# io-bus2.net
KiCad netlist of a schematic drawn in Altium Designer
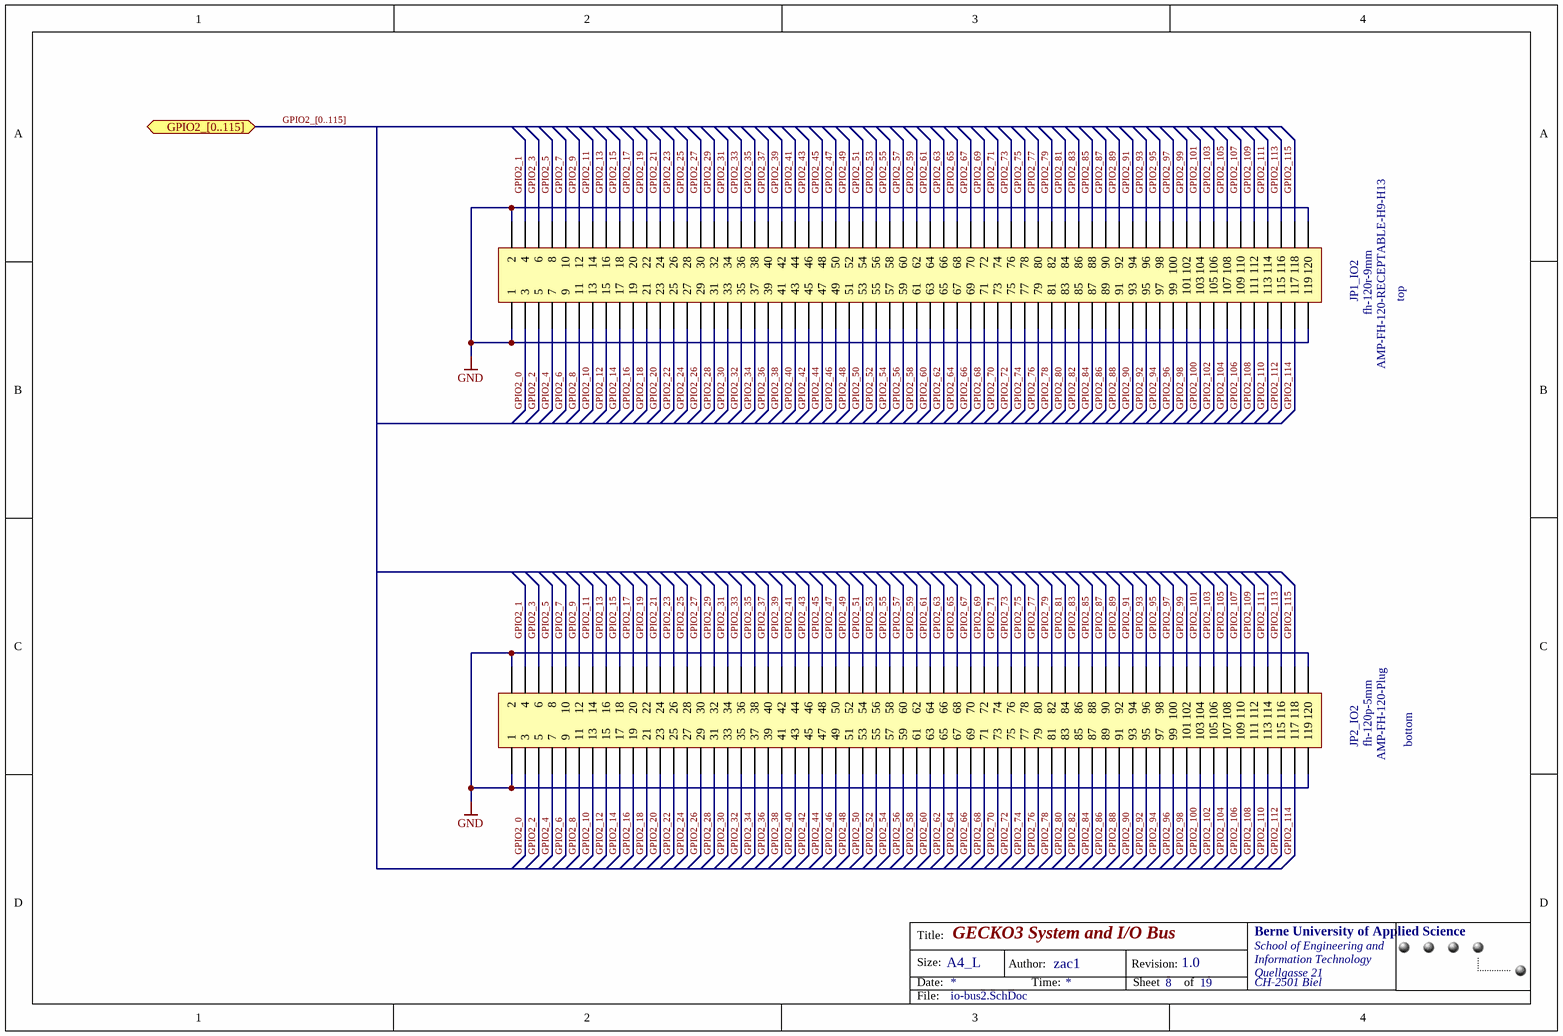
[diagram p0: io-bus2.SchDoc]

(export (version "E")
  (design (tool "Eeschema 10.0.6"))
  (components
    (comp (ref "JP1_IO2")
      (value "AMP-FH-120-RECEPTABLE-H9-H13")
      (footprint "amp_FH_.8mm_120pin_r_H9_H13")
      (description "AMP Free Height System, 0.8mm, 120 Pin, 9 or 13mm Height, Receptable")
      (fields
        (field (name "ALTIUM_VALUE") "fh-120r-9mm")
        (field (name "COMMENT_1") "top")
        (field (name "MANUFACTURER") "AMP")
        (field (name "PART NUMBER") "5-5179009-5")
      )
      (libsource (lib "gecko3-user") (part "AMP-FH-120-RECEPTABLE-H9-H13"))
    )
    (comp (ref "JP2_IO2")
      (value "AMP-FH-120-Plug")
      (footprint "amp_FH_.8mm_120pin_plug")
      (description "AMP Free Height System, 0.8mm, 120 Pin, Plug")
      (fields
        (field (name "COMMENT_1") "bottom")
        (field (name "ALTIUM_VALUE") "fh-120p-5mm")
        (field (name "MANUFACTURER") "AMP")
        (field (name "PART NUMBER") "5177984-5")
      )
      (libsource (lib "gecko3-user") (part "AMP-FH-120-Plug"))
    )
  )
  (nets
    (net (code "1") (name "/GPIO2_0") (class "Default")
      (node (ref "JP1_IO2") (pin "3") (pinfunction "3_3") (pintype "passive"))
      (node (ref "JP2_IO2") (pin "3") (pinfunction "3_3") (pintype "passive"))
    )
    (net (code "2") (name "/GPIO2_1") (class "Default")
      (node (ref "JP1_IO2") (pin "4") (pinfunction "4_4") (pintype "passive"))
      (node (ref "JP2_IO2") (pin "4") (pinfunction "4_4") (pintype "passive"))
    )
    (net (code "3") (name "/GPIO2_2") (class "Default")
      (node (ref "JP1_IO2") (pin "5") (pinfunction "5_5") (pintype "passive"))
      (node (ref "JP2_IO2") (pin "5") (pinfunction "5_5") (pintype "passive"))
    )
    (net (code "4") (name "/GPIO2_3") (class "Default")
      (node (ref "JP1_IO2") (pin "6") (pinfunction "6_6") (pintype "passive"))
      (node (ref "JP2_IO2") (pin "6") (pinfunction "6_6") (pintype "passive"))
    )
    (net (code "5") (name "/GPIO2_4") (class "Default")
      (node (ref "JP1_IO2") (pin "7") (pinfunction "7_7") (pintype "passive"))
      (node (ref "JP2_IO2") (pin "7") (pinfunction "7_7") (pintype "passive"))
    )
    (net (code "6") (name "/GPIO2_5") (class "Default")
      (node (ref "JP1_IO2") (pin "8") (pinfunction "8_8") (pintype "passive"))
      (node (ref "JP2_IO2") (pin "8") (pinfunction "8_8") (pintype "passive"))
    )
    (net (code "7") (name "/GPIO2_6") (class "Default")
      (node (ref "JP1_IO2") (pin "9") (pinfunction "9_9") (pintype "passive"))
      (node (ref "JP2_IO2") (pin "9") (pinfunction "9_9") (pintype "passive"))
    )
    (net (code "8") (name "/GPIO2_7") (class "Default")
      (node (ref "JP1_IO2") (pin "10") (pinfunction "10_10") (pintype "passive"))
      (node (ref "JP2_IO2") (pin "10") (pinfunction "10_10") (pintype "passive"))
    )
    (net (code "9") (name "/GPIO2_8") (class "Default")
      (node (ref "JP1_IO2") (pin "11") (pinfunction "11_11") (pintype "passive"))
      (node (ref "JP2_IO2") (pin "11") (pinfunction "11_11") (pintype "passive"))
    )
    (net (code "10") (name "/GPIO2_9") (class "Default")
      (node (ref "JP1_IO2") (pin "12") (pinfunction "12_12") (pintype "passive"))
      (node (ref "JP2_IO2") (pin "12") (pinfunction "12_12") (pintype "passive"))
    )
    (net (code "11") (name "/GPIO2_10") (class "Default")
      (node (ref "JP1_IO2") (pin "13") (pinfunction "13_13") (pintype "passive"))
      (node (ref "JP2_IO2") (pin "13") (pinfunction "13_13") (pintype "passive"))
    )
    (net (code "12") (name "/GPIO2_11") (class "Default")
      (node (ref "JP1_IO2") (pin "14") (pinfunction "14_14") (pintype "passive"))
      (node (ref "JP2_IO2") (pin "14") (pinfunction "14_14") (pintype "passive"))
    )
    (net (code "13") (name "/GPIO2_12") (class "Default")
      (node (ref "JP1_IO2") (pin "15") (pinfunction "15_15") (pintype "passive"))
      (node (ref "JP2_IO2") (pin "15") (pinfunction "15_15") (pintype "passive"))
    )
    (net (code "14") (name "/GPIO2_13") (class "Default")
      (node (ref "JP1_IO2") (pin "16") (pinfunction "16_16") (pintype "passive"))
      (node (ref "JP2_IO2") (pin "16") (pinfunction "16_16") (pintype "passive"))
    )
    (net (code "15") (name "/GPIO2_14") (class "Default")
      (node (ref "JP1_IO2") (pin "17") (pinfunction "17_17") (pintype "passive"))
      (node (ref "JP2_IO2") (pin "17") (pinfunction "17_17") (pintype "passive"))
    )
    (net (code "16") (name "/GPIO2_15") (class "Default")
      (node (ref "JP1_IO2") (pin "18") (pinfunction "18_18") (pintype "passive"))
      (node (ref "JP2_IO2") (pin "18") (pinfunction "18_18") (pintype "passive"))
    )
    (net (code "17") (name "/GPIO2_16") (class "Default")
      (node (ref "JP1_IO2") (pin "19") (pinfunction "19_19") (pintype "passive"))
      (node (ref "JP2_IO2") (pin "19") (pinfunction "19_19") (pintype "passive"))
    )
    (net (code "18") (name "/GPIO2_17") (class "Default")
      (node (ref "JP1_IO2") (pin "20") (pinfunction "20_20") (pintype "passive"))
      (node (ref "JP2_IO2") (pin "20") (pinfunction "20_20") (pintype "passive"))
    )
    (net (code "19") (name "/GPIO2_18") (class "Default")
      (node (ref "JP1_IO2") (pin "21") (pinfunction "21_21") (pintype "passive"))
      (node (ref "JP2_IO2") (pin "21") (pinfunction "21_21") (pintype "passive"))
    )
    (net (code "20") (name "/GPIO2_19") (class "Default")
      (node (ref "JP1_IO2") (pin "22") (pinfunction "22_22") (pintype "passive"))
      (node (ref "JP2_IO2") (pin "22") (pinfunction "22_22") (pintype "passive"))
    )
    (net (code "21") (name "/GPIO2_20") (class "Default")
      (node (ref "JP1_IO2") (pin "23") (pinfunction "23_23") (pintype "passive"))
      (node (ref "JP2_IO2") (pin "23") (pinfunction "23_23") (pintype "passive"))
    )
    (net (code "22") (name "/GPIO2_21") (class "Default")
      (node (ref "JP1_IO2") (pin "24") (pinfunction "24_24") (pintype "passive"))
      (node (ref "JP2_IO2") (pin "24") (pinfunction "24_24") (pintype "passive"))
    )
    (net (code "23") (name "/GPIO2_22") (class "Default")
      (node (ref "JP1_IO2") (pin "25") (pinfunction "25_25") (pintype "passive"))
      (node (ref "JP2_IO2") (pin "25") (pinfunction "25_25") (pintype "passive"))
    )
    (net (code "24") (name "/GPIO2_23") (class "Default")
      (node (ref "JP1_IO2") (pin "26") (pinfunction "26_26") (pintype "passive"))
      (node (ref "JP2_IO2") (pin "26") (pinfunction "26_26") (pintype "passive"))
    )
    (net (code "25") (name "/GPIO2_24") (class "Default")
      (node (ref "JP1_IO2") (pin "27") (pinfunction "27_27") (pintype "passive"))
      (node (ref "JP2_IO2") (pin "27") (pinfunction "27_27") (pintype "passive"))
    )
    (net (code "26") (name "/GPIO2_25") (class "Default")
      (node (ref "JP1_IO2") (pin "28") (pinfunction "28_28") (pintype "passive"))
      (node (ref "JP2_IO2") (pin "28") (pinfunction "28_28") (pintype "passive"))
    )
    (net (code "27") (name "/GPIO2_26") (class "Default")
      (node (ref "JP1_IO2") (pin "29") (pinfunction "29_29") (pintype "passive"))
      (node (ref "JP2_IO2") (pin "29") (pinfunction "29_29") (pintype "passive"))
    )
    (net (code "28") (name "/GPIO2_27") (class "Default")
      (node (ref "JP1_IO2") (pin "30") (pinfunction "30_30") (pintype "passive"))
      (node (ref "JP2_IO2") (pin "30") (pinfunction "30_30") (pintype "passive"))
    )
    (net (code "29") (name "/GPIO2_28") (class "Default")
      (node (ref "JP1_IO2") (pin "31") (pinfunction "31_31") (pintype "passive"))
      (node (ref "JP2_IO2") (pin "31") (pinfunction "31_31") (pintype "passive"))
    )
    (net (code "30") (name "/GPIO2_29") (class "Default")
      (node (ref "JP1_IO2") (pin "32") (pinfunction "32_32") (pintype "passive"))
      (node (ref "JP2_IO2") (pin "32") (pinfunction "32_32") (pintype "passive"))
    )
    (net (code "31") (name "/GPIO2_30") (class "Default")
      (node (ref "JP1_IO2") (pin "33") (pinfunction "33_33") (pintype "passive"))
      (node (ref "JP2_IO2") (pin "33") (pinfunction "33_33") (pintype "passive"))
    )
    (net (code "32") (name "/GPIO2_31") (class "Default")
      (node (ref "JP1_IO2") (pin "34") (pinfunction "34_34") (pintype "passive"))
      (node (ref "JP2_IO2") (pin "34") (pinfunction "34_34") (pintype "passive"))
    )
    (net (code "33") (name "/GPIO2_32") (class "Default")
      (node (ref "JP1_IO2") (pin "35") (pinfunction "35_35") (pintype "passive"))
      (node (ref "JP2_IO2") (pin "35") (pinfunction "35_35") (pintype "passive"))
    )
    (net (code "34") (name "/GPIO2_33") (class "Default")
      (node (ref "JP1_IO2") (pin "36") (pinfunction "36_36") (pintype "passive"))
      (node (ref "JP2_IO2") (pin "36") (pinfunction "36_36") (pintype "passive"))
    )
    (net (code "35") (name "/GPIO2_34") (class "Default")
      (node (ref "JP1_IO2") (pin "37") (pinfunction "37_37") (pintype "passive"))
      (node (ref "JP2_IO2") (pin "37") (pinfunction "37_37") (pintype "passive"))
    )
    (net (code "36") (name "/GPIO2_35") (class "Default")
      (node (ref "JP1_IO2") (pin "38") (pinfunction "38_38") (pintype "passive"))
      (node (ref "JP2_IO2") (pin "38") (pinfunction "38_38") (pintype "passive"))
    )
    (net (code "37") (name "/GPIO2_36") (class "Default")
      (node (ref "JP1_IO2") (pin "39") (pinfunction "39_39") (pintype "passive"))
      (node (ref "JP2_IO2") (pin "39") (pinfunction "39_39") (pintype "passive"))
    )
    (net (code "38") (name "/GPIO2_37") (class "Default")
      (node (ref "JP1_IO2") (pin "40") (pinfunction "40_40") (pintype "passive"))
      (node (ref "JP2_IO2") (pin "40") (pinfunction "40_40") (pintype "passive"))
    )
    (net (code "39") (name "/GPIO2_38") (class "Default")
      (node (ref "JP1_IO2") (pin "41") (pinfunction "41_41") (pintype "passive"))
      (node (ref "JP2_IO2") (pin "41") (pinfunction "41_41") (pintype "passive"))
    )
    (net (code "40") (name "/GPIO2_39") (class "Default")
      (node (ref "JP1_IO2") (pin "42") (pinfunction "42_42") (pintype "passive"))
      (node (ref "JP2_IO2") (pin "42") (pinfunction "42_42") (pintype "passive"))
    )
    (net (code "41") (name "/GPIO2_40") (class "Default")
      (node (ref "JP1_IO2") (pin "43") (pinfunction "43_43") (pintype "passive"))
      (node (ref "JP2_IO2") (pin "43") (pinfunction "43_43") (pintype "passive"))
    )
    (net (code "42") (name "/GPIO2_41") (class "Default")
      (node (ref "JP1_IO2") (pin "44") (pinfunction "44_44") (pintype "passive"))
      (node (ref "JP2_IO2") (pin "44") (pinfunction "44_44") (pintype "passive"))
    )
    (net (code "43") (name "/GPIO2_42") (class "Default")
      (node (ref "JP1_IO2") (pin "45") (pinfunction "45_45") (pintype "passive"))
      (node (ref "JP2_IO2") (pin "45") (pinfunction "45_45") (pintype "passive"))
    )
    (net (code "44") (name "/GPIO2_43") (class "Default")
      (node (ref "JP1_IO2") (pin "46") (pinfunction "46_46") (pintype "passive"))
      (node (ref "JP2_IO2") (pin "46") (pinfunction "46_46") (pintype "passive"))
    )
    (net (code "45") (name "/GPIO2_44") (class "Default")
      (node (ref "JP1_IO2") (pin "47") (pinfunction "47_47") (pintype "passive"))
      (node (ref "JP2_IO2") (pin "47") (pinfunction "47_47") (pintype "passive"))
    )
    (net (code "46") (name "/GPIO2_45") (class "Default")
      (node (ref "JP1_IO2") (pin "48") (pinfunction "48_48") (pintype "passive"))
      (node (ref "JP2_IO2") (pin "48") (pinfunction "48_48") (pintype "passive"))
    )
    (net (code "47") (name "/GPIO2_46") (class "Default")
      (node (ref "JP1_IO2") (pin "49") (pinfunction "49_49") (pintype "passive"))
      (node (ref "JP2_IO2") (pin "49") (pinfunction "49_49") (pintype "passive"))
    )
    (net (code "48") (name "/GPIO2_47") (class "Default")
      (node (ref "JP1_IO2") (pin "50") (pinfunction "50_50") (pintype "passive"))
      (node (ref "JP2_IO2") (pin "50") (pinfunction "50_50") (pintype "passive"))
    )
    (net (code "49") (name "/GPIO2_48") (class "Default")
      (node (ref "JP1_IO2") (pin "51") (pinfunction "51_51") (pintype "passive"))
      (node (ref "JP2_IO2") (pin "51") (pinfunction "51_51") (pintype "passive"))
    )
    (net (code "50") (name "/GPIO2_49") (class "Default")
      (node (ref "JP1_IO2") (pin "52") (pinfunction "52_52") (pintype "passive"))
      (node (ref "JP2_IO2") (pin "52") (pinfunction "52_52") (pintype "passive"))
    )
    (net (code "51") (name "/GPIO2_50") (class "Default")
      (node (ref "JP1_IO2") (pin "53") (pinfunction "53_53") (pintype "passive"))
      (node (ref "JP2_IO2") (pin "53") (pinfunction "53_53") (pintype "passive"))
    )
    (net (code "52") (name "/GPIO2_51") (class "Default")
      (node (ref "JP1_IO2") (pin "54") (pinfunction "54_54") (pintype "passive"))
      (node (ref "JP2_IO2") (pin "54") (pinfunction "54_54") (pintype "passive"))
    )
    (net (code "53") (name "/GPIO2_52") (class "Default")
      (node (ref "JP1_IO2") (pin "55") (pinfunction "55_55") (pintype "passive"))
      (node (ref "JP2_IO2") (pin "55") (pinfunction "55_55") (pintype "passive"))
    )
    (net (code "54") (name "/GPIO2_53") (class "Default")
      (node (ref "JP1_IO2") (pin "56") (pinfunction "56_56") (pintype "passive"))
      (node (ref "JP2_IO2") (pin "56") (pinfunction "56_56") (pintype "passive"))
    )
    (net (code "55") (name "/GPIO2_54") (class "Default")
      (node (ref "JP1_IO2") (pin "57") (pinfunction "57_57") (pintype "passive"))
      (node (ref "JP2_IO2") (pin "57") (pinfunction "57_57") (pintype "passive"))
    )
    (net (code "56") (name "/GPIO2_55") (class "Default")
      (node (ref "JP1_IO2") (pin "58") (pinfunction "58_58") (pintype "passive"))
      (node (ref "JP2_IO2") (pin "58") (pinfunction "58_58") (pintype "passive"))
    )
    (net (code "57") (name "/GPIO2_56") (class "Default")
      (node (ref "JP1_IO2") (pin "59") (pinfunction "59_59") (pintype "passive"))
      (node (ref "JP2_IO2") (pin "59") (pinfunction "59_59") (pintype "passive"))
    )
    (net (code "58") (name "/GPIO2_57") (class "Default")
      (node (ref "JP1_IO2") (pin "60") (pinfunction "60_60") (pintype "passive"))
      (node (ref "JP2_IO2") (pin "60") (pinfunction "60_60") (pintype "passive"))
    )
    (net (code "59") (name "/GPIO2_58") (class "Default")
      (node (ref "JP1_IO2") (pin "61") (pinfunction "61_61") (pintype "passive"))
      (node (ref "JP2_IO2") (pin "61") (pinfunction "61_61") (pintype "passive"))
    )
    (net (code "60") (name "/GPIO2_59") (class "Default")
      (node (ref "JP1_IO2") (pin "62") (pinfunction "62_62") (pintype "passive"))
      (node (ref "JP2_IO2") (pin "62") (pinfunction "62_62") (pintype "passive"))
    )
    (net (code "61") (name "/GPIO2_60") (class "Default")
      (node (ref "JP1_IO2") (pin "63") (pinfunction "63_63") (pintype "passive"))
      (node (ref "JP2_IO2") (pin "63") (pinfunction "63_63") (pintype "passive"))
    )
    (net (code "62") (name "/GPIO2_61") (class "Default")
      (node (ref "JP1_IO2") (pin "64") (pinfunction "64_64") (pintype "passive"))
      (node (ref "JP2_IO2") (pin "64") (pinfunction "64_64") (pintype "passive"))
    )
    (net (code "63") (name "/GPIO2_62") (class "Default")
      (node (ref "JP1_IO2") (pin "65") (pinfunction "65_65") (pintype "passive"))
      (node (ref "JP2_IO2") (pin "65") (pinfunction "65_65") (pintype "passive"))
    )
    (net (code "64") (name "/GPIO2_63") (class "Default")
      (node (ref "JP1_IO2") (pin "66") (pinfunction "66_66") (pintype "passive"))
      (node (ref "JP2_IO2") (pin "66") (pinfunction "66_66") (pintype "passive"))
    )
    (net (code "65") (name "/GPIO2_64") (class "Default")
      (node (ref "JP1_IO2") (pin "67") (pinfunction "67_67") (pintype "passive"))
      (node (ref "JP2_IO2") (pin "67") (pinfunction "67_67") (pintype "passive"))
    )
    (net (code "66") (name "/GPIO2_65") (class "Default")
      (node (ref "JP1_IO2") (pin "68") (pinfunction "68_68") (pintype "passive"))
      (node (ref "JP2_IO2") (pin "68") (pinfunction "68_68") (pintype "passive"))
    )
    (net (code "67") (name "/GPIO2_66") (class "Default")
      (node (ref "JP1_IO2") (pin "69") (pinfunction "69_69") (pintype "passive"))
      (node (ref "JP2_IO2") (pin "69") (pinfunction "69_69") (pintype "passive"))
    )
    (net (code "68") (name "/GPIO2_67") (class "Default")
      (node (ref "JP1_IO2") (pin "70") (pinfunction "70_70") (pintype "passive"))
      (node (ref "JP2_IO2") (pin "70") (pinfunction "70_70") (pintype "passive"))
    )
    (net (code "69") (name "/GPIO2_68") (class "Default")
      (node (ref "JP1_IO2") (pin "71") (pinfunction "71_71") (pintype "passive"))
      (node (ref "JP2_IO2") (pin "71") (pinfunction "71_71") (pintype "passive"))
    )
    (net (code "70") (name "/GPIO2_69") (class "Default")
      (node (ref "JP1_IO2") (pin "72") (pinfunction "72_72") (pintype "passive"))
      (node (ref "JP2_IO2") (pin "72") (pinfunction "72_72") (pintype "passive"))
    )
    (net (code "71") (name "/GPIO2_70") (class "Default")
      (node (ref "JP1_IO2") (pin "73") (pinfunction "73_73") (pintype "passive"))
      (node (ref "JP2_IO2") (pin "73") (pinfunction "73_73") (pintype "passive"))
    )
    (net (code "72") (name "/GPIO2_71") (class "Default")
      (node (ref "JP1_IO2") (pin "74") (pinfunction "74_74") (pintype "passive"))
      (node (ref "JP2_IO2") (pin "74") (pinfunction "74_74") (pintype "passive"))
    )
    (net (code "73") (name "/GPIO2_72") (class "Default")
      (node (ref "JP1_IO2") (pin "75") (pinfunction "75_75") (pintype "passive"))
      (node (ref "JP2_IO2") (pin "75") (pinfunction "75_75") (pintype "passive"))
    )
    (net (code "74") (name "/GPIO2_73") (class "Default")
      (node (ref "JP1_IO2") (pin "76") (pinfunction "76_76") (pintype "passive"))
      (node (ref "JP2_IO2") (pin "76") (pinfunction "76_76") (pintype "passive"))
    )
    (net (code "75") (name "/GPIO2_74") (class "Default")
      (node (ref "JP1_IO2") (pin "77") (pinfunction "77_77") (pintype "passive"))
      (node (ref "JP2_IO2") (pin "77") (pinfunction "77_77") (pintype "passive"))
    )
    (net (code "76") (name "/GPIO2_75") (class "Default")
      (node (ref "JP1_IO2") (pin "78") (pinfunction "78_78") (pintype "passive"))
      (node (ref "JP2_IO2") (pin "78") (pinfunction "78_78") (pintype "passive"))
    )
    (net (code "77") (name "/GPIO2_76") (class "Default")
      (node (ref "JP1_IO2") (pin "79") (pinfunction "79_79") (pintype "passive"))
      (node (ref "JP2_IO2") (pin "79") (pinfunction "79_79") (pintype "passive"))
    )
    (net (code "78") (name "/GPIO2_77") (class "Default")
      (node (ref "JP1_IO2") (pin "80") (pinfunction "80_80") (pintype "passive"))
      (node (ref "JP2_IO2") (pin "80") (pinfunction "80_80") (pintype "passive"))
    )
    (net (code "79") (name "/GPIO2_78") (class "Default")
      (node (ref "JP1_IO2") (pin "81") (pinfunction "81_81") (pintype "passive"))
      (node (ref "JP2_IO2") (pin "81") (pinfunction "81_81") (pintype "passive"))
    )
    (net (code "80") (name "/GPIO2_79") (class "Default")
      (node (ref "JP1_IO2") (pin "82") (pinfunction "82_82") (pintype "passive"))
      (node (ref "JP2_IO2") (pin "82") (pinfunction "82_82") (pintype "passive"))
    )
    (net (code "81") (name "/GPIO2_80") (class "Default")
      (node (ref "JP1_IO2") (pin "83") (pinfunction "83_83") (pintype "passive"))
      (node (ref "JP2_IO2") (pin "83") (pinfunction "83_83") (pintype "passive"))
    )
    (net (code "82") (name "/GPIO2_81") (class "Default")
      (node (ref "JP1_IO2") (pin "84") (pinfunction "84_84") (pintype "passive"))
      (node (ref "JP2_IO2") (pin "84") (pinfunction "84_84") (pintype "passive"))
    )
    (net (code "83") (name "/GPIO2_82") (class "Default")
      (node (ref "JP1_IO2") (pin "85") (pinfunction "85_85") (pintype "passive"))
      (node (ref "JP2_IO2") (pin "85") (pinfunction "85_85") (pintype "passive"))
    )
    (net (code "84") (name "/GPIO2_83") (class "Default")
      (node (ref "JP1_IO2") (pin "86") (pinfunction "86_86") (pintype "passive"))
      (node (ref "JP2_IO2") (pin "86") (pinfunction "86_86") (pintype "passive"))
    )
    (net (code "85") (name "/GPIO2_84") (class "Default")
      (node (ref "JP1_IO2") (pin "87") (pinfunction "87_87") (pintype "passive"))
      (node (ref "JP2_IO2") (pin "87") (pinfunction "87_87") (pintype "passive"))
    )
    (net (code "86") (name "/GPIO2_85") (class "Default")
      (node (ref "JP1_IO2") (pin "88") (pinfunction "88_88") (pintype "passive"))
      (node (ref "JP2_IO2") (pin "88") (pinfunction "88_88") (pintype "passive"))
    )
    (net (code "87") (name "/GPIO2_86") (class "Default")
      (node (ref "JP1_IO2") (pin "89") (pinfunction "89_89") (pintype "passive"))
      (node (ref "JP2_IO2") (pin "89") (pinfunction "89_89") (pintype "passive"))
    )
    (net (code "88") (name "/GPIO2_87") (class "Default")
      (node (ref "JP1_IO2") (pin "90") (pinfunction "90_90") (pintype "passive"))
      (node (ref "JP2_IO2") (pin "90") (pinfunction "90_90") (pintype "passive"))
    )
    (net (code "89") (name "/GPIO2_88") (class "Default")
      (node (ref "JP1_IO2") (pin "91") (pinfunction "91_91") (pintype "passive"))
      (node (ref "JP2_IO2") (pin "91") (pinfunction "91_91") (pintype "passive"))
    )
    (net (code "90") (name "/GPIO2_89") (class "Default")
      (node (ref "JP1_IO2") (pin "92") (pinfunction "92_92") (pintype "passive"))
      (node (ref "JP2_IO2") (pin "92") (pinfunction "92_92") (pintype "passive"))
    )
    (net (code "91") (name "/GPIO2_90") (class "Default")
      (node (ref "JP1_IO2") (pin "93") (pinfunction "93_93") (pintype "passive"))
      (node (ref "JP2_IO2") (pin "93") (pinfunction "93_93") (pintype "passive"))
    )
    (net (code "92") (name "/GPIO2_91") (class "Default")
      (node (ref "JP1_IO2") (pin "94") (pinfunction "94_94") (pintype "passive"))
      (node (ref "JP2_IO2") (pin "94") (pinfunction "94_94") (pintype "passive"))
    )
    (net (code "93") (name "/GPIO2_92") (class "Default")
      (node (ref "JP1_IO2") (pin "95") (pinfunction "95_95") (pintype "passive"))
      (node (ref "JP2_IO2") (pin "95") (pinfunction "95_95") (pintype "passive"))
    )
    (net (code "94") (name "/GPIO2_93") (class "Default")
      (node (ref "JP1_IO2") (pin "96") (pinfunction "96_96") (pintype "passive"))
      (node (ref "JP2_IO2") (pin "96") (pinfunction "96_96") (pintype "passive"))
    )
    (net (code "95") (name "/GPIO2_94") (class "Default")
      (node (ref "JP1_IO2") (pin "97") (pinfunction "97_97") (pintype "passive"))
      (node (ref "JP2_IO2") (pin "97") (pinfunction "97_97") (pintype "passive"))
    )
    (net (code "96") (name "/GPIO2_95") (class "Default")
      (node (ref "JP1_IO2") (pin "98") (pinfunction "98_98") (pintype "passive"))
      (node (ref "JP2_IO2") (pin "98") (pinfunction "98_98") (pintype "passive"))
    )
    (net (code "97") (name "/GPIO2_96") (class "Default")
      (node (ref "JP1_IO2") (pin "99") (pinfunction "99_99") (pintype "passive"))
      (node (ref "JP2_IO2") (pin "99") (pinfunction "99_99") (pintype "passive"))
    )
    (net (code "98") (name "/GPIO2_97") (class "Default")
      (node (ref "JP1_IO2") (pin "100") (pinfunction "100_100") (pintype "passive"))
      (node (ref "JP2_IO2") (pin "100") (pinfunction "100_100") (pintype "passive"))
    )
    (net (code "99") (name "/GPIO2_98") (class "Default")
      (node (ref "JP1_IO2") (pin "101") (pinfunction "101_101") (pintype "passive"))
      (node (ref "JP2_IO2") (pin "101") (pinfunction "101_101") (pintype "passive"))
    )
    (net (code "100") (name "/GPIO2_99") (class "Default")
      (node (ref "JP1_IO2") (pin "102") (pinfunction "102_102") (pintype "passive"))
      (node (ref "JP2_IO2") (pin "102") (pinfunction "102_102") (pintype "passive"))
    )
    (net (code "101") (name "/GPIO2_100") (class "Default")
      (node (ref "JP1_IO2") (pin "103") (pinfunction "103_103") (pintype "passive"))
      (node (ref "JP2_IO2") (pin "103") (pinfunction "103_103") (pintype "passive"))
    )
    (net (code "102") (name "/GPIO2_101") (class "Default")
      (node (ref "JP1_IO2") (pin "104") (pinfunction "104_104") (pintype "passive"))
      (node (ref "JP2_IO2") (pin "104") (pinfunction "104_104") (pintype "passive"))
    )
    (net (code "103") (name "/GPIO2_102") (class "Default")
      (node (ref "JP1_IO2") (pin "105") (pinfunction "105_105") (pintype "passive"))
      (node (ref "JP2_IO2") (pin "105") (pinfunction "105_105") (pintype "passive"))
    )
    (net (code "104") (name "/GPIO2_103") (class "Default")
      (node (ref "JP1_IO2") (pin "106") (pinfunction "106_106") (pintype "passive"))
      (node (ref "JP2_IO2") (pin "106") (pinfunction "106_106") (pintype "passive"))
    )
    (net (code "105") (name "/GPIO2_104") (class "Default")
      (node (ref "JP1_IO2") (pin "107") (pinfunction "107_107") (pintype "passive"))
      (node (ref "JP2_IO2") (pin "107") (pinfunction "107_107") (pintype "passive"))
    )
    (net (code "106") (name "/GPIO2_105") (class "Default")
      (node (ref "JP1_IO2") (pin "108") (pinfunction "108_108") (pintype "passive"))
      (node (ref "JP2_IO2") (pin "108") (pinfunction "108_108") (pintype "passive"))
    )
    (net (code "107") (name "/GPIO2_106") (class "Default")
      (node (ref "JP1_IO2") (pin "109") (pinfunction "109_109") (pintype "passive"))
      (node (ref "JP2_IO2") (pin "109") (pinfunction "109_109") (pintype "passive"))
    )
    (net (code "108") (name "/GPIO2_107") (class "Default")
      (node (ref "JP1_IO2") (pin "110") (pinfunction "110_110") (pintype "passive"))
      (node (ref "JP2_IO2") (pin "110") (pinfunction "110_110") (pintype "passive"))
    )
    (net (code "109") (name "/GPIO2_108") (class "Default")
      (node (ref "JP1_IO2") (pin "111") (pinfunction "111_111") (pintype "passive"))
      (node (ref "JP2_IO2") (pin "111") (pinfunction "111_111") (pintype "passive"))
    )
    (net (code "110") (name "/GPIO2_109") (class "Default")
      (node (ref "JP1_IO2") (pin "112") (pinfunction "112_112") (pintype "passive"))
      (node (ref "JP2_IO2") (pin "112") (pinfunction "112_112") (pintype "passive"))
    )
    (net (code "111") (name "/GPIO2_110") (class "Default")
      (node (ref "JP1_IO2") (pin "113") (pinfunction "113_113") (pintype "passive"))
      (node (ref "JP2_IO2") (pin "113") (pinfunction "113_113") (pintype "passive"))
    )
    (net (code "112") (name "/GPIO2_111") (class "Default")
      (node (ref "JP1_IO2") (pin "114") (pinfunction "114_114") (pintype "passive"))
      (node (ref "JP2_IO2") (pin "114") (pinfunction "114_114") (pintype "passive"))
    )
    (net (code "113") (name "/GPIO2_112") (class "Default")
      (node (ref "JP1_IO2") (pin "115") (pinfunction "115_115") (pintype "passive"))
      (node (ref "JP2_IO2") (pin "115") (pinfunction "115_115") (pintype "passive"))
    )
    (net (code "114") (name "/GPIO2_113") (class "Default")
      (node (ref "JP1_IO2") (pin "116") (pinfunction "116_116") (pintype "passive"))
      (node (ref "JP2_IO2") (pin "116") (pinfunction "116_116") (pintype "passive"))
    )
    (net (code "115") (name "/GPIO2_114") (class "Default")
      (node (ref "JP1_IO2") (pin "117") (pinfunction "117_117") (pintype "passive"))
      (node (ref "JP2_IO2") (pin "117") (pinfunction "117_117") (pintype "passive"))
    )
    (net (code "116") (name "/GPIO2_115") (class "Default")
      (node (ref "JP1_IO2") (pin "118") (pinfunction "118_118") (pintype "passive"))
      (node (ref "JP2_IO2") (pin "118") (pinfunction "118_118") (pintype "passive"))
    )
    (net (code "118") (name "GND") (class "Default")
      (node (ref "JP1_IO2") (pin "1") (pinfunction "1_1") (pintype "passive"))
      (node (ref "JP1_IO2") (pin "119") (pinfunction "119_119") (pintype "passive"))
      (node (ref "JP1_IO2") (pin "120") (pinfunction "120_120") (pintype "passive"))
      (node (ref "JP1_IO2") (pin "2") (pinfunction "2_2") (pintype "passive"))
      (node (ref "JP2_IO2") (pin "1") (pinfunction "1_1") (pintype "passive"))
      (node (ref "JP2_IO2") (pin "119") (pinfunction "119_119") (pintype "passive"))
      (node (ref "JP2_IO2") (pin "120") (pinfunction "120_120") (pintype "passive"))
      (node (ref "JP2_IO2") (pin "2") (pinfunction "2_2") (pintype "passive"))
    )
  )
)
